# S151A.net
KiCad netlist of a schematic drawn in EAGLE
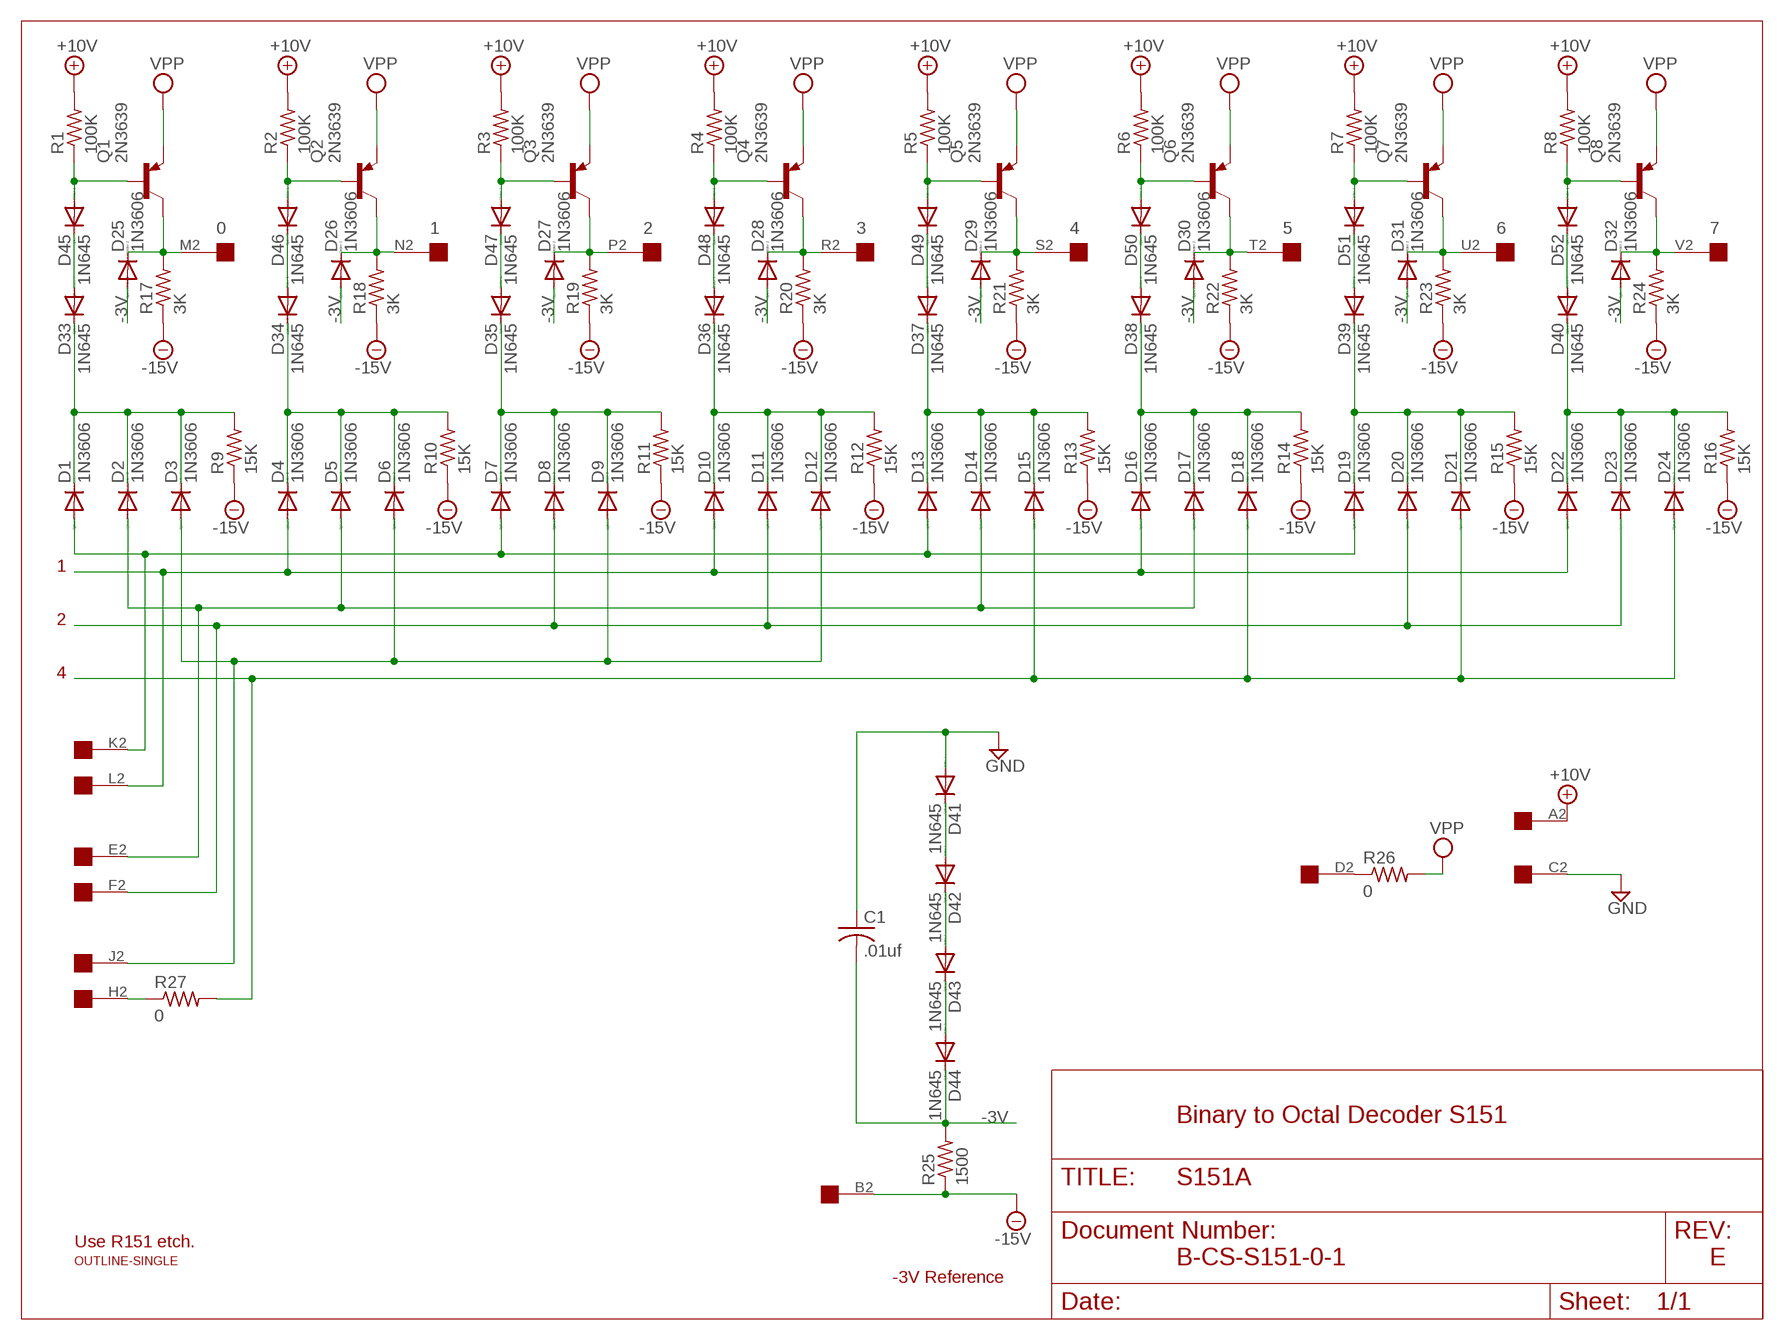
[diagram p0: schematic, sheet 1]

(export (version "E")
  (design (tool "Eeschema 10.0.6"))
  (components
    (comp (ref "C1")
      (value ".01uf")
      (footprint "eagle-import:C050-025X075")
      (libsource (lib "eagle-import") (part "C-US050-025X075"))
    )
    (comp (ref "D1")
      (value "1N3606")
      (footprint "eagle-import:DO35-10")
      (libsource (lib "eagle-import") (part "1N4148DO35-10"))
    )
    (comp (ref "D2")
      (value "1N3606")
      (footprint "eagle-import:DO35-10")
      (libsource (lib "eagle-import") (part "1N4148DO35-10"))
    )
    (comp (ref "D3")
      (value "1N3606")
      (footprint "eagle-import:DO35-10")
      (libsource (lib "eagle-import") (part "1N4148DO35-10"))
    )
    (comp (ref "D4")
      (value "1N3606")
      (footprint "eagle-import:DO35-10")
      (libsource (lib "eagle-import") (part "1N4148DO35-10"))
    )
    (comp (ref "D5")
      (value "1N3606")
      (footprint "eagle-import:DO35-10")
      (libsource (lib "eagle-import") (part "1N4148DO35-10"))
    )
    (comp (ref "D6")
      (value "1N3606")
      (footprint "eagle-import:DO35-10")
      (libsource (lib "eagle-import") (part "1N4148DO35-10"))
    )
    (comp (ref "D7")
      (value "1N3606")
      (footprint "eagle-import:DO35-10")
      (libsource (lib "eagle-import") (part "1N4148DO35-10"))
    )
    (comp (ref "D8")
      (value "1N3606")
      (footprint "eagle-import:DO35-10")
      (libsource (lib "eagle-import") (part "1N4148DO35-10"))
    )
    (comp (ref "D9")
      (value "1N3606")
      (footprint "eagle-import:DO35-10")
      (libsource (lib "eagle-import") (part "1N4148DO35-10"))
    )
    (comp (ref "D10")
      (value "1N3606")
      (footprint "eagle-import:DO35-10")
      (libsource (lib "eagle-import") (part "1N4148DO35-10"))
    )
    (comp (ref "D11")
      (value "1N3606")
      (footprint "eagle-import:DO35-10")
      (libsource (lib "eagle-import") (part "1N4148DO35-10"))
    )
    (comp (ref "D12")
      (value "1N3606")
      (footprint "eagle-import:DO35-10")
      (libsource (lib "eagle-import") (part "1N4148DO35-10"))
    )
    (comp (ref "D13")
      (value "1N3606")
      (footprint "eagle-import:DO35-10")
      (libsource (lib "eagle-import") (part "1N4148DO35-10"))
    )
    (comp (ref "D14")
      (value "1N3606")
      (footprint "eagle-import:DO35-10")
      (libsource (lib "eagle-import") (part "1N4148DO35-10"))
    )
    (comp (ref "D15")
      (value "1N3606")
      (footprint "eagle-import:DO35-10")
      (libsource (lib "eagle-import") (part "1N4148DO35-10"))
    )
    (comp (ref "D16")
      (value "1N3606")
      (footprint "eagle-import:DO35-10")
      (libsource (lib "eagle-import") (part "1N4148DO35-10"))
    )
    (comp (ref "D17")
      (value "1N3606")
      (footprint "eagle-import:DO35-10")
      (libsource (lib "eagle-import") (part "1N4148DO35-10"))
    )
    (comp (ref "D18")
      (value "1N3606")
      (footprint "eagle-import:DO35-10")
      (libsource (lib "eagle-import") (part "1N4148DO35-10"))
    )
    (comp (ref "D19")
      (value "1N3606")
      (footprint "eagle-import:DO35-10")
      (libsource (lib "eagle-import") (part "1N4148DO35-10"))
    )
    (comp (ref "D20")
      (value "1N3606")
      (footprint "eagle-import:DO35-10")
      (libsource (lib "eagle-import") (part "1N4148DO35-10"))
    )
    (comp (ref "D21")
      (value "1N3606")
      (footprint "eagle-import:DO35-10")
      (libsource (lib "eagle-import") (part "1N4148DO35-10"))
    )
    (comp (ref "D22")
      (value "1N3606")
      (footprint "eagle-import:DO35-10")
      (libsource (lib "eagle-import") (part "1N4148DO35-10"))
    )
    (comp (ref "D23")
      (value "1N3606")
      (footprint "eagle-import:DO35-10")
      (libsource (lib "eagle-import") (part "1N4148DO35-10"))
    )
    (comp (ref "D24")
      (value "1N3606")
      (footprint "eagle-import:DO35-10")
      (libsource (lib "eagle-import") (part "1N4148DO35-10"))
    )
    (comp (ref "D25")
      (value "1N3606")
      (footprint "eagle-import:DO35-10")
      (libsource (lib "eagle-import") (part "1N4148DO35-10"))
    )
    (comp (ref "D26")
      (value "1N3606")
      (footprint "eagle-import:DO35-10")
      (libsource (lib "eagle-import") (part "1N4148DO35-10"))
    )
    (comp (ref "D27")
      (value "1N3606")
      (footprint "eagle-import:DO35-10")
      (libsource (lib "eagle-import") (part "1N4148DO35-10"))
    )
    (comp (ref "D28")
      (value "1N3606")
      (footprint "eagle-import:DO35-10")
      (libsource (lib "eagle-import") (part "1N4148DO35-10"))
    )
    (comp (ref "D29")
      (value "1N3606")
      (footprint "eagle-import:DO35-10")
      (libsource (lib "eagle-import") (part "1N4148DO35-10"))
    )
    (comp (ref "D30")
      (value "1N3606")
      (footprint "eagle-import:DO35-10")
      (libsource (lib "eagle-import") (part "1N4148DO35-10"))
    )
    (comp (ref "D31")
      (value "1N3606")
      (footprint "eagle-import:DO35-10")
      (libsource (lib "eagle-import") (part "1N4148DO35-10"))
    )
    (comp (ref "D32")
      (value "1N3606")
      (footprint "eagle-import:DO35-10")
      (libsource (lib "eagle-import") (part "1N4148DO35-10"))
    )
    (comp (ref "D33")
      (value "1N645")
      (footprint "eagle-import:DO35-10")
      (libsource (lib "eagle-import") (part "1N4148DO35-10"))
    )
    (comp (ref "D34")
      (value "1N645")
      (footprint "eagle-import:DO35-10")
      (libsource (lib "eagle-import") (part "1N4148DO35-10"))
    )
    (comp (ref "D35")
      (value "1N645")
      (footprint "eagle-import:DO35-10")
      (libsource (lib "eagle-import") (part "1N4148DO35-10"))
    )
    (comp (ref "D36")
      (value "1N645")
      (footprint "eagle-import:DO35-10")
      (libsource (lib "eagle-import") (part "1N4148DO35-10"))
    )
    (comp (ref "D37")
      (value "1N645")
      (footprint "eagle-import:DO35-10")
      (libsource (lib "eagle-import") (part "1N4148DO35-10"))
    )
    (comp (ref "D38")
      (value "1N645")
      (footprint "eagle-import:DO35-10")
      (libsource (lib "eagle-import") (part "1N4148DO35-10"))
    )
    (comp (ref "D39")
      (value "1N645")
      (footprint "eagle-import:DO35-10")
      (libsource (lib "eagle-import") (part "1N4148DO35-10"))
    )
    (comp (ref "D40")
      (value "1N645")
      (footprint "eagle-import:DO35-10")
      (libsource (lib "eagle-import") (part "1N4148DO35-10"))
    )
    (comp (ref "D41")
      (value "1N645")
      (footprint "eagle-import:DO35-10")
      (libsource (lib "eagle-import") (part "1N4148DO35-10"))
    )
    (comp (ref "D42")
      (value "1N645")
      (footprint "eagle-import:DO35-10")
      (libsource (lib "eagle-import") (part "1N4148DO35-10"))
    )
    (comp (ref "D43")
      (value "1N645")
      (footprint "eagle-import:DO35-10")
      (libsource (lib "eagle-import") (part "1N4148DO35-10"))
    )
    (comp (ref "D44")
      (value "1N645")
      (footprint "eagle-import:DO35-10")
      (libsource (lib "eagle-import") (part "1N4148DO35-10"))
    )
    (comp (ref "D45")
      (value "1N645")
      (footprint "eagle-import:DO35-10")
      (libsource (lib "eagle-import") (part "1N4148DO35-10"))
    )
    (comp (ref "D46")
      (value "1N645")
      (footprint "eagle-import:DO35-10")
      (libsource (lib "eagle-import") (part "1N4148DO35-10"))
    )
    (comp (ref "D47")
      (value "1N645")
      (footprint "eagle-import:DO35-10")
      (libsource (lib "eagle-import") (part "1N4148DO35-10"))
    )
    (comp (ref "D48")
      (value "1N645")
      (footprint "eagle-import:DO35-10")
      (libsource (lib "eagle-import") (part "1N4148DO35-10"))
    )
    (comp (ref "D49")
      (value "1N645")
      (footprint "eagle-import:DO35-10")
      (libsource (lib "eagle-import") (part "1N4148DO35-10"))
    )
    (comp (ref "D50")
      (value "1N645")
      (footprint "eagle-import:DO35-10")
      (libsource (lib "eagle-import") (part "1N4148DO35-10"))
    )
    (comp (ref "D51")
      (value "1N645")
      (footprint "eagle-import:DO35-10")
      (libsource (lib "eagle-import") (part "1N4148DO35-10"))
    )
    (comp (ref "D52")
      (value "1N645")
      (footprint "eagle-import:DO35-10")
      (libsource (lib "eagle-import") (part "1N4148DO35-10"))
    )
    (comp (ref "Q1")
      (value "2N3639")
      (footprint "eagle-import:TO39")
      (libsource (lib "eagle-import") (part "2N3637"))
    )
    (comp (ref "Q2")
      (value "2N3639")
      (footprint "eagle-import:TO39")
      (libsource (lib "eagle-import") (part "2N3637"))
    )
    (comp (ref "Q3")
      (value "2N3639")
      (footprint "eagle-import:TO39")
      (libsource (lib "eagle-import") (part "2N3637"))
    )
    (comp (ref "Q4")
      (value "2N3639")
      (footprint "eagle-import:TO39")
      (libsource (lib "eagle-import") (part "2N3637"))
    )
    (comp (ref "Q5")
      (value "2N3639")
      (footprint "eagle-import:TO39")
      (libsource (lib "eagle-import") (part "2N3637"))
    )
    (comp (ref "Q6")
      (value "2N3639")
      (footprint "eagle-import:TO39")
      (libsource (lib "eagle-import") (part "2N3637"))
    )
    (comp (ref "Q7")
      (value "2N3639")
      (footprint "eagle-import:TO39")
      (libsource (lib "eagle-import") (part "2N3637"))
    )
    (comp (ref "Q8")
      (value "2N3639")
      (footprint "eagle-import:TO39")
      (libsource (lib "eagle-import") (part "2N3637"))
    )
    (comp (ref "R1")
      (value "100K")
      (footprint "eagle-import:0207_10")
      (libsource (lib "eagle-import") (part "R-US_0207/10"))
    )
    (comp (ref "R2")
      (value "100K")
      (footprint "eagle-import:0207_10")
      (libsource (lib "eagle-import") (part "R-US_0207/10"))
    )
    (comp (ref "R3")
      (value "100K")
      (footprint "eagle-import:0207_10")
      (libsource (lib "eagle-import") (part "R-US_0207/10"))
    )
    (comp (ref "R4")
      (value "100K")
      (footprint "eagle-import:0207_10")
      (libsource (lib "eagle-import") (part "R-US_0207/10"))
    )
    (comp (ref "R5")
      (value "100K")
      (footprint "eagle-import:0207_10")
      (libsource (lib "eagle-import") (part "R-US_0207/10"))
    )
    (comp (ref "R6")
      (value "100K")
      (footprint "eagle-import:0207_10")
      (libsource (lib "eagle-import") (part "R-US_0207/10"))
    )
    (comp (ref "R7")
      (value "100K")
      (footprint "eagle-import:0207_10")
      (libsource (lib "eagle-import") (part "R-US_0207/10"))
    )
    (comp (ref "R8")
      (value "100K")
      (footprint "eagle-import:0207_10")
      (libsource (lib "eagle-import") (part "R-US_0207/10"))
    )
    (comp (ref "R9")
      (value "15K")
      (footprint "eagle-import:0207_10")
      (libsource (lib "eagle-import") (part "R-US_0207/10"))
    )
    (comp (ref "R10")
      (value "15K")
      (footprint "eagle-import:0207_10")
      (libsource (lib "eagle-import") (part "R-US_0207/10"))
    )
    (comp (ref "R11")
      (value "15K")
      (footprint "eagle-import:0207_10")
      (libsource (lib "eagle-import") (part "R-US_0207/10"))
    )
    (comp (ref "R12")
      (value "15K")
      (footprint "eagle-import:0207_10")
      (libsource (lib "eagle-import") (part "R-US_0207/10"))
    )
    (comp (ref "R13")
      (value "15K")
      (footprint "eagle-import:0207_10")
      (libsource (lib "eagle-import") (part "R-US_0207/10"))
    )
    (comp (ref "R14")
      (value "15K")
      (footprint "eagle-import:0207_10")
      (libsource (lib "eagle-import") (part "R-US_0207/10"))
    )
    (comp (ref "R15")
      (value "15K")
      (footprint "eagle-import:0207_10")
      (libsource (lib "eagle-import") (part "R-US_0207/10"))
    )
    (comp (ref "R16")
      (value "15K")
      (footprint "eagle-import:0207_10")
      (libsource (lib "eagle-import") (part "R-US_0207/10"))
    )
    (comp (ref "R17")
      (value "3K")
      (footprint "eagle-import:0207_10")
      (libsource (lib "eagle-import") (part "R-US_0207/10"))
    )
    (comp (ref "R18")
      (value "3K")
      (footprint "eagle-import:0207_10")
      (libsource (lib "eagle-import") (part "R-US_0207/10"))
    )
    (comp (ref "R19")
      (value "3K")
      (footprint "eagle-import:0207_10")
      (libsource (lib "eagle-import") (part "R-US_0207/10"))
    )
    (comp (ref "R20")
      (value "3K")
      (footprint "eagle-import:0207_10")
      (libsource (lib "eagle-import") (part "R-US_0207/10"))
    )
    (comp (ref "R21")
      (value "3K")
      (footprint "eagle-import:0207_10")
      (libsource (lib "eagle-import") (part "R-US_0207/10"))
    )
    (comp (ref "R22")
      (value "3K")
      (footprint "eagle-import:0207_10")
      (libsource (lib "eagle-import") (part "R-US_0207/10"))
    )
    (comp (ref "R23")
      (value "3K")
      (footprint "eagle-import:0207_10")
      (libsource (lib "eagle-import") (part "R-US_0207/10"))
    )
    (comp (ref "R24")
      (value "3K")
      (footprint "eagle-import:0207_10")
      (libsource (lib "eagle-import") (part "R-US_0207/10"))
    )
    (comp (ref "R25")
      (value "1500")
      (footprint "eagle-import:0207_10")
      (libsource (lib "eagle-import") (part "R-US_0207/10"))
    )
    (comp (ref "R26")
      (value "0")
      (footprint "eagle-import:0207_10")
      (libsource (lib "eagle-import") (part "R-US_0207/10"))
    )
    (comp (ref "R27")
      (value "0")
      (footprint "eagle-import:0207_10")
      (libsource (lib "eagle-import") (part "R-US_0207/10"))
    )
    (comp (ref "U$1")
      (value "OUTLINE-SINGLE")
      (footprint "eagle-import:SINGLE")
      (libsource (lib "eagle-import") (part "OUTLINE-SINGLE"))
    )
    (comp (ref "U$2")
      (value "EDGE-1")
      (footprint "eagle-import:EDGE-CON1")
      (libsource (lib "eagle-import") (part "EDGE-1"))
    )
  )
  (nets
    (net (code "1") (name "+10V") (class "Default")
      (node (ref "R1") (pin "2") (pinfunction "2_2") (pintype "passive"))
      (node (ref "R2") (pin "2") (pinfunction "2_2") (pintype "passive"))
      (node (ref "R3") (pin "2") (pinfunction "2_2") (pintype "passive"))
      (node (ref "R4") (pin "2") (pinfunction "2_2") (pintype "passive"))
      (node (ref "R5") (pin "2") (pinfunction "2_2") (pintype "passive"))
      (node (ref "R6") (pin "2") (pinfunction "2_2") (pintype "passive"))
      (node (ref "R7") (pin "2") (pinfunction "2_2") (pintype "passive"))
      (node (ref "R8") (pin "2") (pinfunction "2_2") (pintype "passive"))
      (node (ref "U$2") (pin "A2") (pinfunction "1_A2") (pintype "bidirectional"))
    )
    (net (code "2") (name "-15V") (class "Default")
      (node (ref "R10") (pin "1") (pinfunction "1_1") (pintype "passive"))
      (node (ref "R11") (pin "1") (pinfunction "1_1") (pintype "passive"))
      (node (ref "R12") (pin "1") (pinfunction "1_1") (pintype "passive"))
      (node (ref "R13") (pin "1") (pinfunction "1_1") (pintype "passive"))
      (node (ref "R14") (pin "1") (pinfunction "1_1") (pintype "passive"))
      (node (ref "R15") (pin "1") (pinfunction "1_1") (pintype "passive"))
      (node (ref "R16") (pin "1") (pinfunction "1_1") (pintype "passive"))
      (node (ref "R17") (pin "1") (pinfunction "1_1") (pintype "passive"))
      (node (ref "R18") (pin "1") (pinfunction "1_1") (pintype "passive"))
      (node (ref "R19") (pin "1") (pinfunction "1_1") (pintype "passive"))
      (node (ref "R20") (pin "1") (pinfunction "1_1") (pintype "passive"))
      (node (ref "R21") (pin "1") (pinfunction "1_1") (pintype "passive"))
      (node (ref "R22") (pin "1") (pinfunction "1_1") (pintype "passive"))
      (node (ref "R23") (pin "1") (pinfunction "1_1") (pintype "passive"))
      (node (ref "R24") (pin "1") (pinfunction "1_1") (pintype "passive"))
      (node (ref "R25") (pin "1") (pinfunction "1_1") (pintype "passive"))
      (node (ref "R9") (pin "1") (pinfunction "1_1") (pintype "passive"))
      (node (ref "U$2") (pin "B2") (pinfunction "1_B2") (pintype "bidirectional"))
    )
    (net (code "3") (name "/-3V") (class "Default")
      (node (ref "C1") (pin "2") (pinfunction "2_2") (pintype "passive"))
      (node (ref "D25") (pin "A") (pinfunction "A_A") (pintype "passive"))
      (node (ref "D26") (pin "A") (pinfunction "A_A") (pintype "passive"))
      (node (ref "D27") (pin "A") (pinfunction "A_A") (pintype "passive"))
      (node (ref "D28") (pin "A") (pinfunction "A_A") (pintype "passive"))
      (node (ref "D29") (pin "A") (pinfunction "A_A") (pintype "passive"))
      (node (ref "D30") (pin "A") (pinfunction "A_A") (pintype "passive"))
      (node (ref "D31") (pin "A") (pinfunction "A_A") (pintype "passive"))
      (node (ref "D32") (pin "A") (pinfunction "A_A") (pintype "passive"))
      (node (ref "D44") (pin "C") (pinfunction "C_C") (pintype "passive"))
      (node (ref "R25") (pin "2") (pinfunction "2_2") (pintype "passive"))
    )
    (net (code "4") (name "/0") (class "Default")
      (node (ref "D25") (pin "C") (pinfunction "C_C") (pintype "passive"))
      (node (ref "Q1") (pin "3") (pinfunction "C_3") (pintype "passive"))
      (node (ref "R17") (pin "2") (pinfunction "2_2") (pintype "passive"))
      (node (ref "U$2") (pin "M2") (pinfunction "1_M2") (pintype "bidirectional"))
    )
    (net (code "5") (name "/1") (class "Default")
      (node (ref "D26") (pin "C") (pinfunction "C_C") (pintype "passive"))
      (node (ref "Q2") (pin "3") (pinfunction "C_3") (pintype "passive"))
      (node (ref "R18") (pin "2") (pinfunction "2_2") (pintype "passive"))
      (node (ref "U$2") (pin "N2") (pinfunction "1_N2") (pintype "bidirectional"))
    )
    (net (code "6") (name "/2") (class "Default")
      (node (ref "D27") (pin "C") (pinfunction "C_C") (pintype "passive"))
      (node (ref "Q3") (pin "3") (pinfunction "C_3") (pintype "passive"))
      (node (ref "R19") (pin "2") (pinfunction "2_2") (pintype "passive"))
      (node (ref "U$2") (pin "P2") (pinfunction "1_P2") (pintype "bidirectional"))
    )
    (net (code "7") (name "/3") (class "Default")
      (node (ref "D28") (pin "C") (pinfunction "C_C") (pintype "passive"))
      (node (ref "Q4") (pin "3") (pinfunction "C_3") (pintype "passive"))
      (node (ref "R20") (pin "2") (pinfunction "2_2") (pintype "passive"))
      (node (ref "U$2") (pin "R2") (pinfunction "1_R2") (pintype "bidirectional"))
    )
    (net (code "8") (name "/4") (class "Default")
      (node (ref "D29") (pin "C") (pinfunction "C_C") (pintype "passive"))
      (node (ref "Q5") (pin "3") (pinfunction "C_3") (pintype "passive"))
      (node (ref "R21") (pin "2") (pinfunction "2_2") (pintype "passive"))
      (node (ref "U$2") (pin "S2") (pinfunction "1_S2") (pintype "bidirectional"))
    )
    (net (code "9") (name "/5") (class "Default")
      (node (ref "D30") (pin "C") (pinfunction "C_C") (pintype "passive"))
      (node (ref "Q6") (pin "3") (pinfunction "C_3") (pintype "passive"))
      (node (ref "R22") (pin "2") (pinfunction "2_2") (pintype "passive"))
      (node (ref "U$2") (pin "T2") (pinfunction "1_T2") (pintype "bidirectional"))
    )
    (net (code "10") (name "/6") (class "Default")
      (node (ref "D31") (pin "C") (pinfunction "C_C") (pintype "passive"))
      (node (ref "Q7") (pin "3") (pinfunction "C_3") (pintype "passive"))
      (node (ref "R23") (pin "2") (pinfunction "2_2") (pintype "passive"))
      (node (ref "U$2") (pin "U2") (pinfunction "1_U2") (pintype "bidirectional"))
    )
    (net (code "11") (name "/7") (class "Default")
      (node (ref "D32") (pin "C") (pinfunction "C_C") (pintype "passive"))
      (node (ref "Q8") (pin "3") (pinfunction "C_3") (pintype "passive"))
      (node (ref "R24") (pin "2") (pinfunction "2_2") (pintype "passive"))
      (node (ref "U$2") (pin "V2") (pinfunction "1_V2") (pintype "bidirectional"))
    )
    (net (code "12") (name "GND") (class "Default")
      (node (ref "C1") (pin "1") (pinfunction "1_1") (pintype "passive"))
      (node (ref "D41") (pin "A") (pinfunction "A_A") (pintype "passive"))
      (node (ref "U$2") (pin "C2") (pinfunction "1_C2") (pintype "bidirectional"))
    )
    (net (code "13") (name "Net-(D1-PadC)") (class "Default")
      (node (ref "D1") (pin "C") (pinfunction "C_C") (pintype "passive"))
      (node (ref "D2") (pin "C") (pinfunction "C_C") (pintype "passive"))
      (node (ref "D3") (pin "C") (pinfunction "C_C") (pintype "passive"))
      (node (ref "D33") (pin "C") (pinfunction "C_C") (pintype "passive"))
      (node (ref "R9") (pin "2") (pinfunction "2_2") (pintype "passive"))
    )
    (net (code "14") (name "Net-(D10-PadC)") (class "Default")
      (node (ref "D10") (pin "C") (pinfunction "C_C") (pintype "passive"))
      (node (ref "D11") (pin "C") (pinfunction "C_C") (pintype "passive"))
      (node (ref "D12") (pin "C") (pinfunction "C_C") (pintype "passive"))
      (node (ref "D36") (pin "C") (pinfunction "C_C") (pintype "passive"))
      (node (ref "R12") (pin "2") (pinfunction "2_2") (pintype "passive"))
    )
    (net (code "15") (name "Net-(D13-PadC)") (class "Default")
      (node (ref "D13") (pin "C") (pinfunction "C_C") (pintype "passive"))
      (node (ref "D14") (pin "C") (pinfunction "C_C") (pintype "passive"))
      (node (ref "D15") (pin "C") (pinfunction "C_C") (pintype "passive"))
      (node (ref "D37") (pin "C") (pinfunction "C_C") (pintype "passive"))
      (node (ref "R13") (pin "2") (pinfunction "2_2") (pintype "passive"))
    )
    (net (code "16") (name "Net-(D15-PadA)") (class "Default")
      (node (ref "D15") (pin "A") (pinfunction "A_A") (pintype "passive"))
      (node (ref "D18") (pin "A") (pinfunction "A_A") (pintype "passive"))
      (node (ref "D21") (pin "A") (pinfunction "A_A") (pintype "passive"))
      (node (ref "D24") (pin "A") (pinfunction "A_A") (pintype "passive"))
      (node (ref "R27") (pin "2") (pinfunction "2_2") (pintype "passive"))
    )
    (net (code "17") (name "Net-(D16-PadC)") (class "Default")
      (node (ref "D16") (pin "C") (pinfunction "C_C") (pintype "passive"))
      (node (ref "D17") (pin "C") (pinfunction "C_C") (pintype "passive"))
      (node (ref "D18") (pin "C") (pinfunction "C_C") (pintype "passive"))
      (node (ref "D38") (pin "C") (pinfunction "C_C") (pintype "passive"))
      (node (ref "R14") (pin "2") (pinfunction "2_2") (pintype "passive"))
    )
    (net (code "18") (name "Net-(D19-PadC)") (class "Default")
      (node (ref "D19") (pin "C") (pinfunction "C_C") (pintype "passive"))
      (node (ref "D20") (pin "C") (pinfunction "C_C") (pintype "passive"))
      (node (ref "D21") (pin "C") (pinfunction "C_C") (pintype "passive"))
      (node (ref "D39") (pin "C") (pinfunction "C_C") (pintype "passive"))
      (node (ref "R15") (pin "2") (pinfunction "2_2") (pintype "passive"))
    )
    (net (code "19") (name "Net-(D22-PadC)") (class "Default")
      (node (ref "D22") (pin "C") (pinfunction "C_C") (pintype "passive"))
      (node (ref "D23") (pin "C") (pinfunction "C_C") (pintype "passive"))
      (node (ref "D24") (pin "C") (pinfunction "C_C") (pintype "passive"))
      (node (ref "D40") (pin "C") (pinfunction "C_C") (pintype "passive"))
      (node (ref "R16") (pin "2") (pinfunction "2_2") (pintype "passive"))
    )
    (net (code "20") (name "Net-(D33-PadA)") (class "Default")
      (node (ref "D33") (pin "A") (pinfunction "A_A") (pintype "passive"))
      (node (ref "D45") (pin "C") (pinfunction "C_C") (pintype "passive"))
    )
    (net (code "21") (name "Net-(D34-PadA)") (class "Default")
      (node (ref "D34") (pin "A") (pinfunction "A_A") (pintype "passive"))
      (node (ref "D46") (pin "C") (pinfunction "C_C") (pintype "passive"))
    )
    (net (code "22") (name "Net-(D34-PadC)") (class "Default")
      (node (ref "D34") (pin "C") (pinfunction "C_C") (pintype "passive"))
      (node (ref "D4") (pin "C") (pinfunction "C_C") (pintype "passive"))
      (node (ref "D5") (pin "C") (pinfunction "C_C") (pintype "passive"))
      (node (ref "D6") (pin "C") (pinfunction "C_C") (pintype "passive"))
      (node (ref "R10") (pin "2") (pinfunction "2_2") (pintype "passive"))
    )
    (net (code "23") (name "Net-(D35-PadA)") (class "Default")
      (node (ref "D35") (pin "A") (pinfunction "A_A") (pintype "passive"))
      (node (ref "D47") (pin "C") (pinfunction "C_C") (pintype "passive"))
    )
    (net (code "24") (name "Net-(D35-PadC)") (class "Default")
      (node (ref "D35") (pin "C") (pinfunction "C_C") (pintype "passive"))
      (node (ref "D7") (pin "C") (pinfunction "C_C") (pintype "passive"))
      (node (ref "D8") (pin "C") (pinfunction "C_C") (pintype "passive"))
      (node (ref "D9") (pin "C") (pinfunction "C_C") (pintype "passive"))
      (node (ref "R11") (pin "2") (pinfunction "2_2") (pintype "passive"))
    )
    (net (code "25") (name "Net-(D36-PadA)") (class "Default")
      (node (ref "D36") (pin "A") (pinfunction "A_A") (pintype "passive"))
      (node (ref "D48") (pin "C") (pinfunction "C_C") (pintype "passive"))
    )
    (net (code "26") (name "Net-(D37-PadA)") (class "Default")
      (node (ref "D37") (pin "A") (pinfunction "A_A") (pintype "passive"))
      (node (ref "D49") (pin "C") (pinfunction "C_C") (pintype "passive"))
    )
    (net (code "27") (name "Net-(D38-PadA)") (class "Default")
      (node (ref "D38") (pin "A") (pinfunction "A_A") (pintype "passive"))
      (node (ref "D50") (pin "C") (pinfunction "C_C") (pintype "passive"))
    )
    (net (code "28") (name "Net-(D39-PadA)") (class "Default")
      (node (ref "D39") (pin "A") (pinfunction "A_A") (pintype "passive"))
      (node (ref "D51") (pin "C") (pinfunction "C_C") (pintype "passive"))
    )
    (net (code "29") (name "Net-(D40-PadA)") (class "Default")
      (node (ref "D40") (pin "A") (pinfunction "A_A") (pintype "passive"))
      (node (ref "D52") (pin "C") (pinfunction "C_C") (pintype "passive"))
    )
    (net (code "30") (name "Net-(D41-PadC)") (class "Default")
      (node (ref "D41") (pin "C") (pinfunction "C_C") (pintype "passive"))
      (node (ref "D42") (pin "A") (pinfunction "A_A") (pintype "passive"))
    )
    (net (code "31") (name "Net-(D42-PadC)") (class "Default")
      (node (ref "D42") (pin "C") (pinfunction "C_C") (pintype "passive"))
      (node (ref "D43") (pin "A") (pinfunction "A_A") (pintype "passive"))
    )
    (net (code "32") (name "Net-(D43-PadC)") (class "Default")
      (node (ref "D43") (pin "C") (pinfunction "C_C") (pintype "passive"))
      (node (ref "D44") (pin "A") (pinfunction "A_A") (pintype "passive"))
    )
    (net (code "33") (name "Net-(Q1-B)") (class "Default")
      (node (ref "D45") (pin "A") (pinfunction "A_A") (pintype "passive"))
      (node (ref "Q1") (pin "2") (pinfunction "B_2") (pintype "passive"))
      (node (ref "R1") (pin "1") (pinfunction "1_1") (pintype "passive"))
    )
    (net (code "34") (name "Net-(Q2-B)") (class "Default")
      (node (ref "D46") (pin "A") (pinfunction "A_A") (pintype "passive"))
      (node (ref "Q2") (pin "2") (pinfunction "B_2") (pintype "passive"))
      (node (ref "R2") (pin "1") (pinfunction "1_1") (pintype "passive"))
    )
    (net (code "35") (name "Net-(Q3-B)") (class "Default")
      (node (ref "D47") (pin "A") (pinfunction "A_A") (pintype "passive"))
      (node (ref "Q3") (pin "2") (pinfunction "B_2") (pintype "passive"))
      (node (ref "R3") (pin "1") (pinfunction "1_1") (pintype "passive"))
    )
    (net (code "36") (name "Net-(Q4-B)") (class "Default")
      (node (ref "D48") (pin "A") (pinfunction "A_A") (pintype "passive"))
      (node (ref "Q4") (pin "2") (pinfunction "B_2") (pintype "passive"))
      (node (ref "R4") (pin "1") (pinfunction "1_1") (pintype "passive"))
    )
    (net (code "37") (name "Net-(Q5-B)") (class "Default")
      (node (ref "D49") (pin "A") (pinfunction "A_A") (pintype "passive"))
      (node (ref "Q5") (pin "2") (pinfunction "B_2") (pintype "passive"))
      (node (ref "R5") (pin "1") (pinfunction "1_1") (pintype "passive"))
    )
    (net (code "38") (name "Net-(Q6-B)") (class "Default")
      (node (ref "D50") (pin "A") (pinfunction "A_A") (pintype "passive"))
      (node (ref "Q6") (pin "2") (pinfunction "B_2") (pintype "passive"))
      (node (ref "R6") (pin "1") (pinfunction "1_1") (pintype "passive"))
    )
    (net (code "39") (name "Net-(Q7-B)") (class "Default")
      (node (ref "D51") (pin "A") (pinfunction "A_A") (pintype "passive"))
      (node (ref "Q7") (pin "2") (pinfunction "B_2") (pintype "passive"))
      (node (ref "R7") (pin "1") (pinfunction "1_1") (pintype "passive"))
    )
    (net (code "40") (name "Net-(Q8-B)") (class "Default")
      (node (ref "D52") (pin "A") (pinfunction "A_A") (pintype "passive"))
      (node (ref "Q8") (pin "2") (pinfunction "B_2") (pintype "passive"))
      (node (ref "R8") (pin "1") (pinfunction "1_1") (pintype "passive"))
    )
    (net (code "41") (name "Net-(U$2D-1)") (class "Default")
      (node (ref "R26") (pin "1") (pinfunction "1_1") (pintype "passive"))
      (node (ref "U$2") (pin "D2") (pinfunction "1_D2") (pintype "bidirectional"))
    )
    (net (code "42") (name "Net-(U$2E-1)") (class "Default")
      (node (ref "D14") (pin "A") (pinfunction "A_A") (pintype "passive"))
      (node (ref "D17") (pin "A") (pinfunction "A_A") (pintype "passive"))
      (node (ref "D2") (pin "A") (pinfunction "A_A") (pintype "passive"))
      (node (ref "D5") (pin "A") (pinfunction "A_A") (pintype "passive"))
      (node (ref "U$2") (pin "E2") (pinfunction "1_E2") (pintype "bidirectional"))
    )
    (net (code "43") (name "Net-(U$2F-1)") (class "Default")
      (node (ref "D11") (pin "A") (pinfunction "A_A") (pintype "passive"))
      (node (ref "D20") (pin "A") (pinfunction "A_A") (pintype "passive"))
      (node (ref "D23") (pin "A") (pinfunction "A_A") (pintype "passive"))
      (node (ref "D8") (pin "A") (pinfunction "A_A") (pintype "passive"))
      (node (ref "U$2") (pin "F2") (pinfunction "1_F2") (pintype "bidirectional"))
    )
    (net (code "44") (name "Net-(U$2G-1)") (class "Default")
      (node (ref "R27") (pin "1") (pinfunction "1_1") (pintype "passive"))
      (node (ref "U$2") (pin "H2") (pinfunction "1_H2") (pintype "bidirectional"))
    )
    (net (code "45") (name "Net-(U$2H-1)") (class "Default")
      (node (ref "D12") (pin "A") (pinfunction "A_A") (pintype "passive"))
      (node (ref "D3") (pin "A") (pinfunction "A_A") (pintype "passive"))
      (node (ref "D6") (pin "A") (pinfunction "A_A") (pintype "passive"))
      (node (ref "D9") (pin "A") (pinfunction "A_A") (pintype "passive"))
      (node (ref "U$2") (pin "J2") (pinfunction "1_J2") (pintype "bidirectional"))
    )
    (net (code "46") (name "Net-(U$2I-1)") (class "Default")
      (node (ref "D1") (pin "A") (pinfunction "A_A") (pintype "passive"))
      (node (ref "D13") (pin "A") (pinfunction "A_A") (pintype "passive"))
      (node (ref "D19") (pin "A") (pinfunction "A_A") (pintype "passive"))
      (node (ref "D7") (pin "A") (pinfunction "A_A") (pintype "passive"))
      (node (ref "U$2") (pin "K2") (pinfunction "1_K2") (pintype "bidirectional"))
    )
    (net (code "47") (name "Net-(U$2J-1)") (class "Default")
      (node (ref "D10") (pin "A") (pinfunction "A_A") (pintype "passive"))
      (node (ref "D16") (pin "A") (pinfunction "A_A") (pintype "passive"))
      (node (ref "D22") (pin "A") (pinfunction "A_A") (pintype "passive"))
      (node (ref "D4") (pin "A") (pinfunction "A_A") (pintype "passive"))
      (node (ref "U$2") (pin "L2") (pinfunction "1_L2") (pintype "bidirectional"))
    )
    (net (code "48") (name "VPP") (class "Default")
      (node (ref "Q1") (pin "1") (pinfunction "E_1") (pintype "passive"))
      (node (ref "Q2") (pin "1") (pinfunction "E_1") (pintype "passive"))
      (node (ref "Q3") (pin "1") (pinfunction "E_1") (pintype "passive"))
      (node (ref "Q4") (pin "1") (pinfunction "E_1") (pintype "passive"))
      (node (ref "Q5") (pin "1") (pinfunction "E_1") (pintype "passive"))
      (node (ref "Q6") (pin "1") (pinfunction "E_1") (pintype "passive"))
      (node (ref "Q7") (pin "1") (pinfunction "E_1") (pintype "passive"))
      (node (ref "Q8") (pin "1") (pinfunction "E_1") (pintype "passive"))
      (node (ref "R26") (pin "2") (pinfunction "2_2") (pintype "passive"))
    )
  )
)
